# switches_annotated.net
KiCad netlist of a schematic drawn in EAGLE
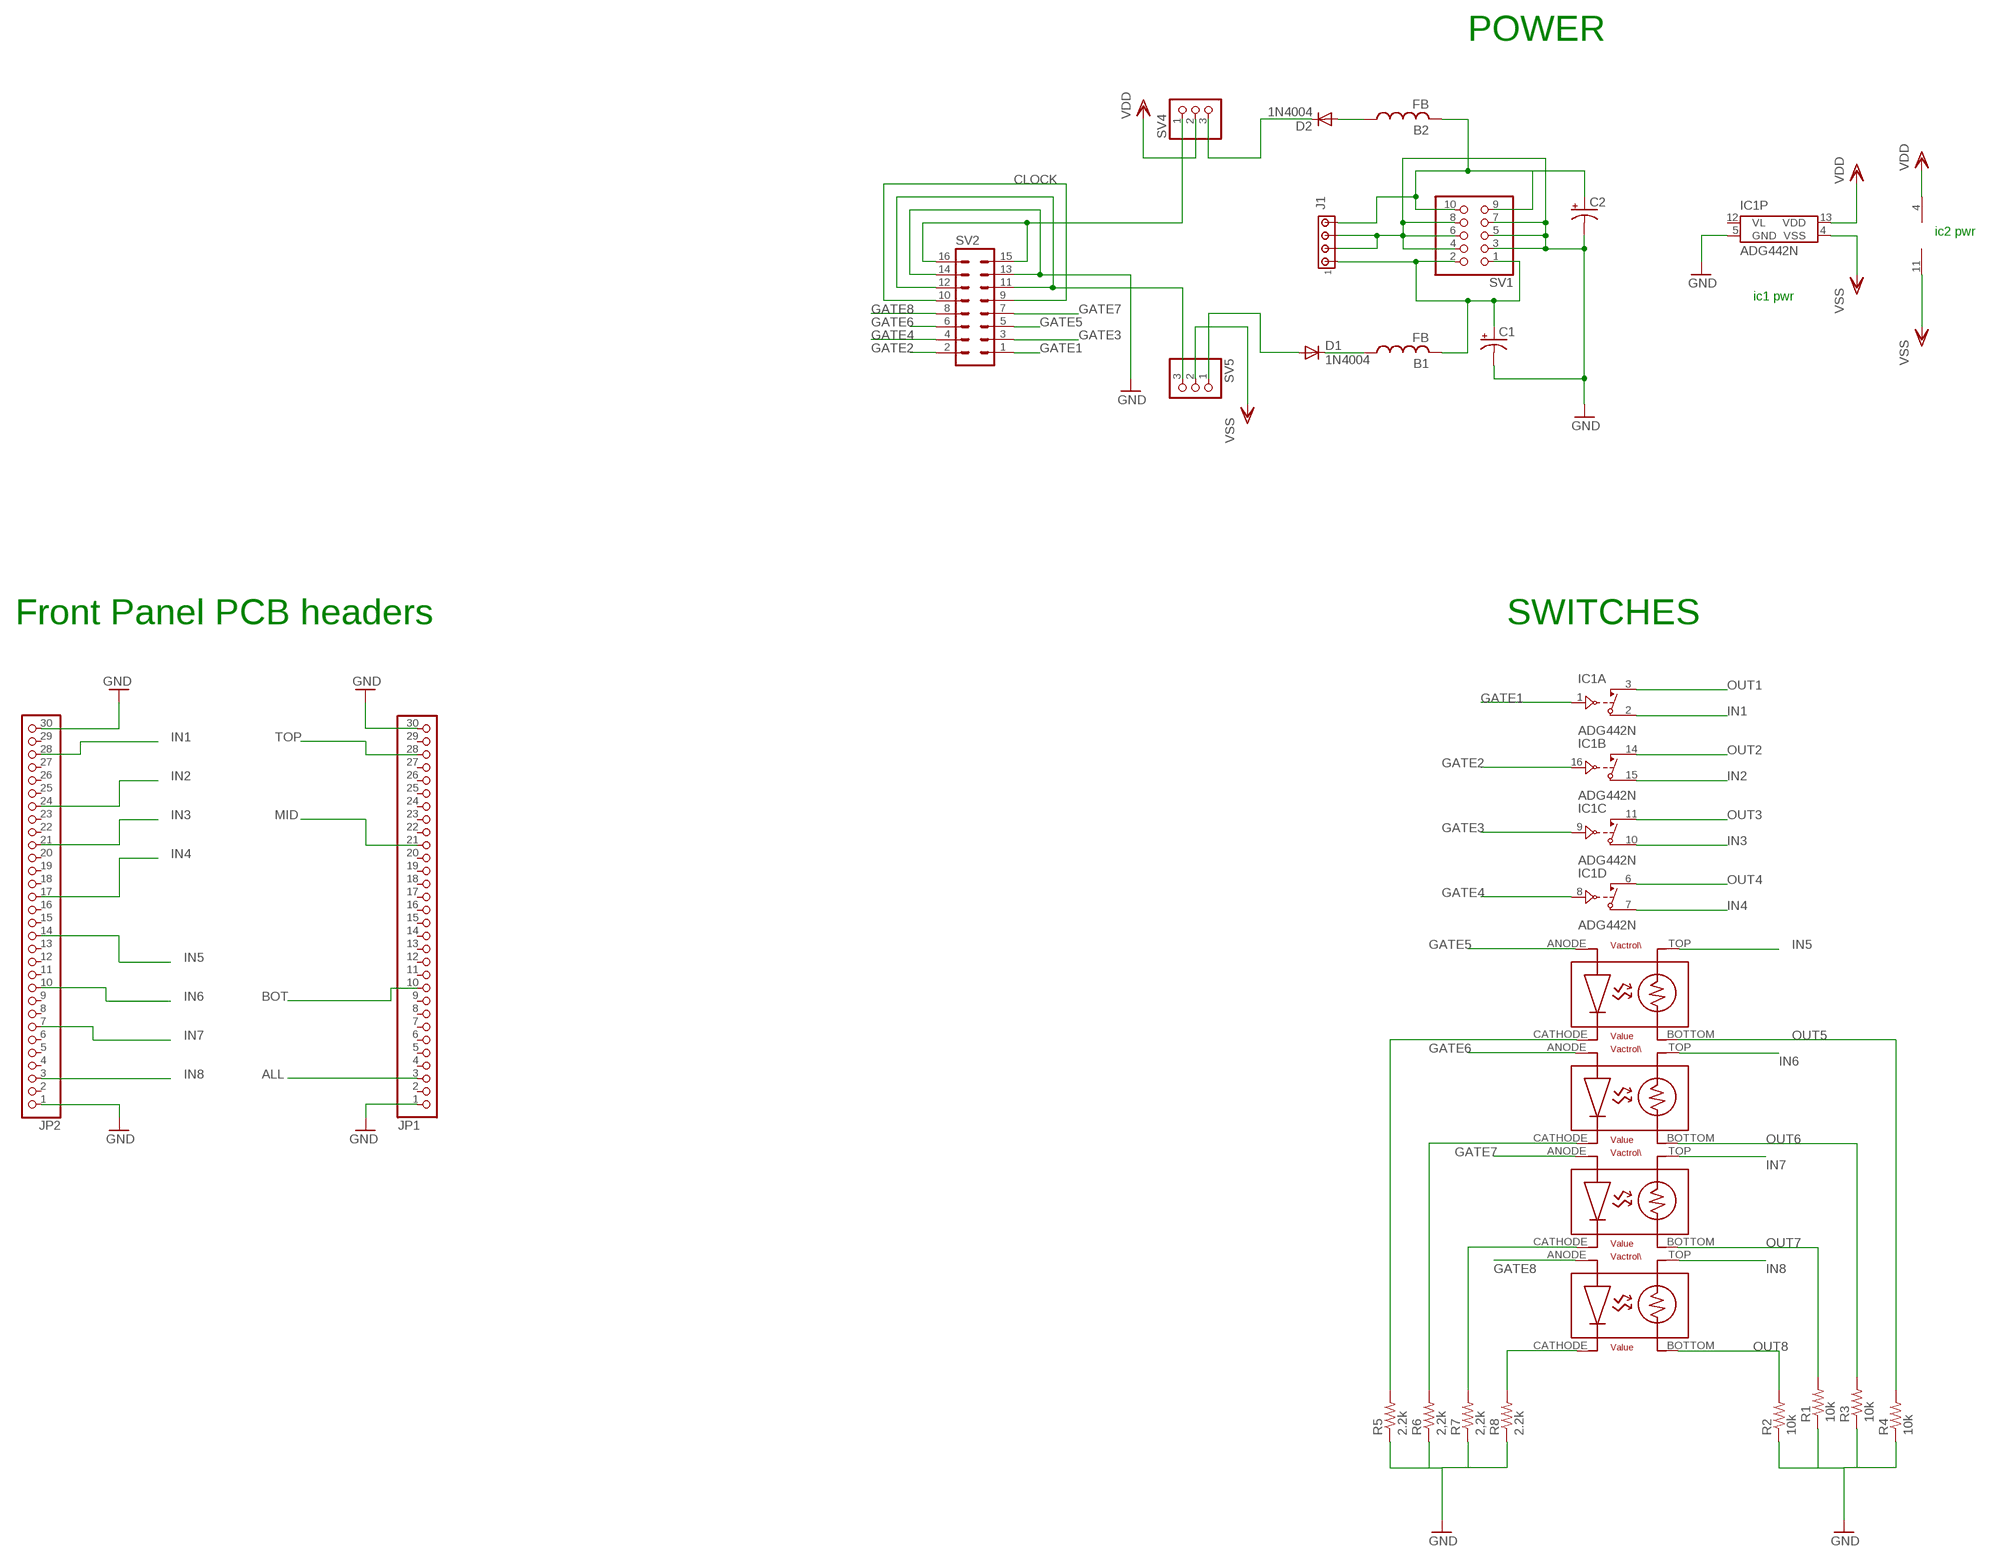
[diagram p0: schematic, sheet 1, part 1 of 2]
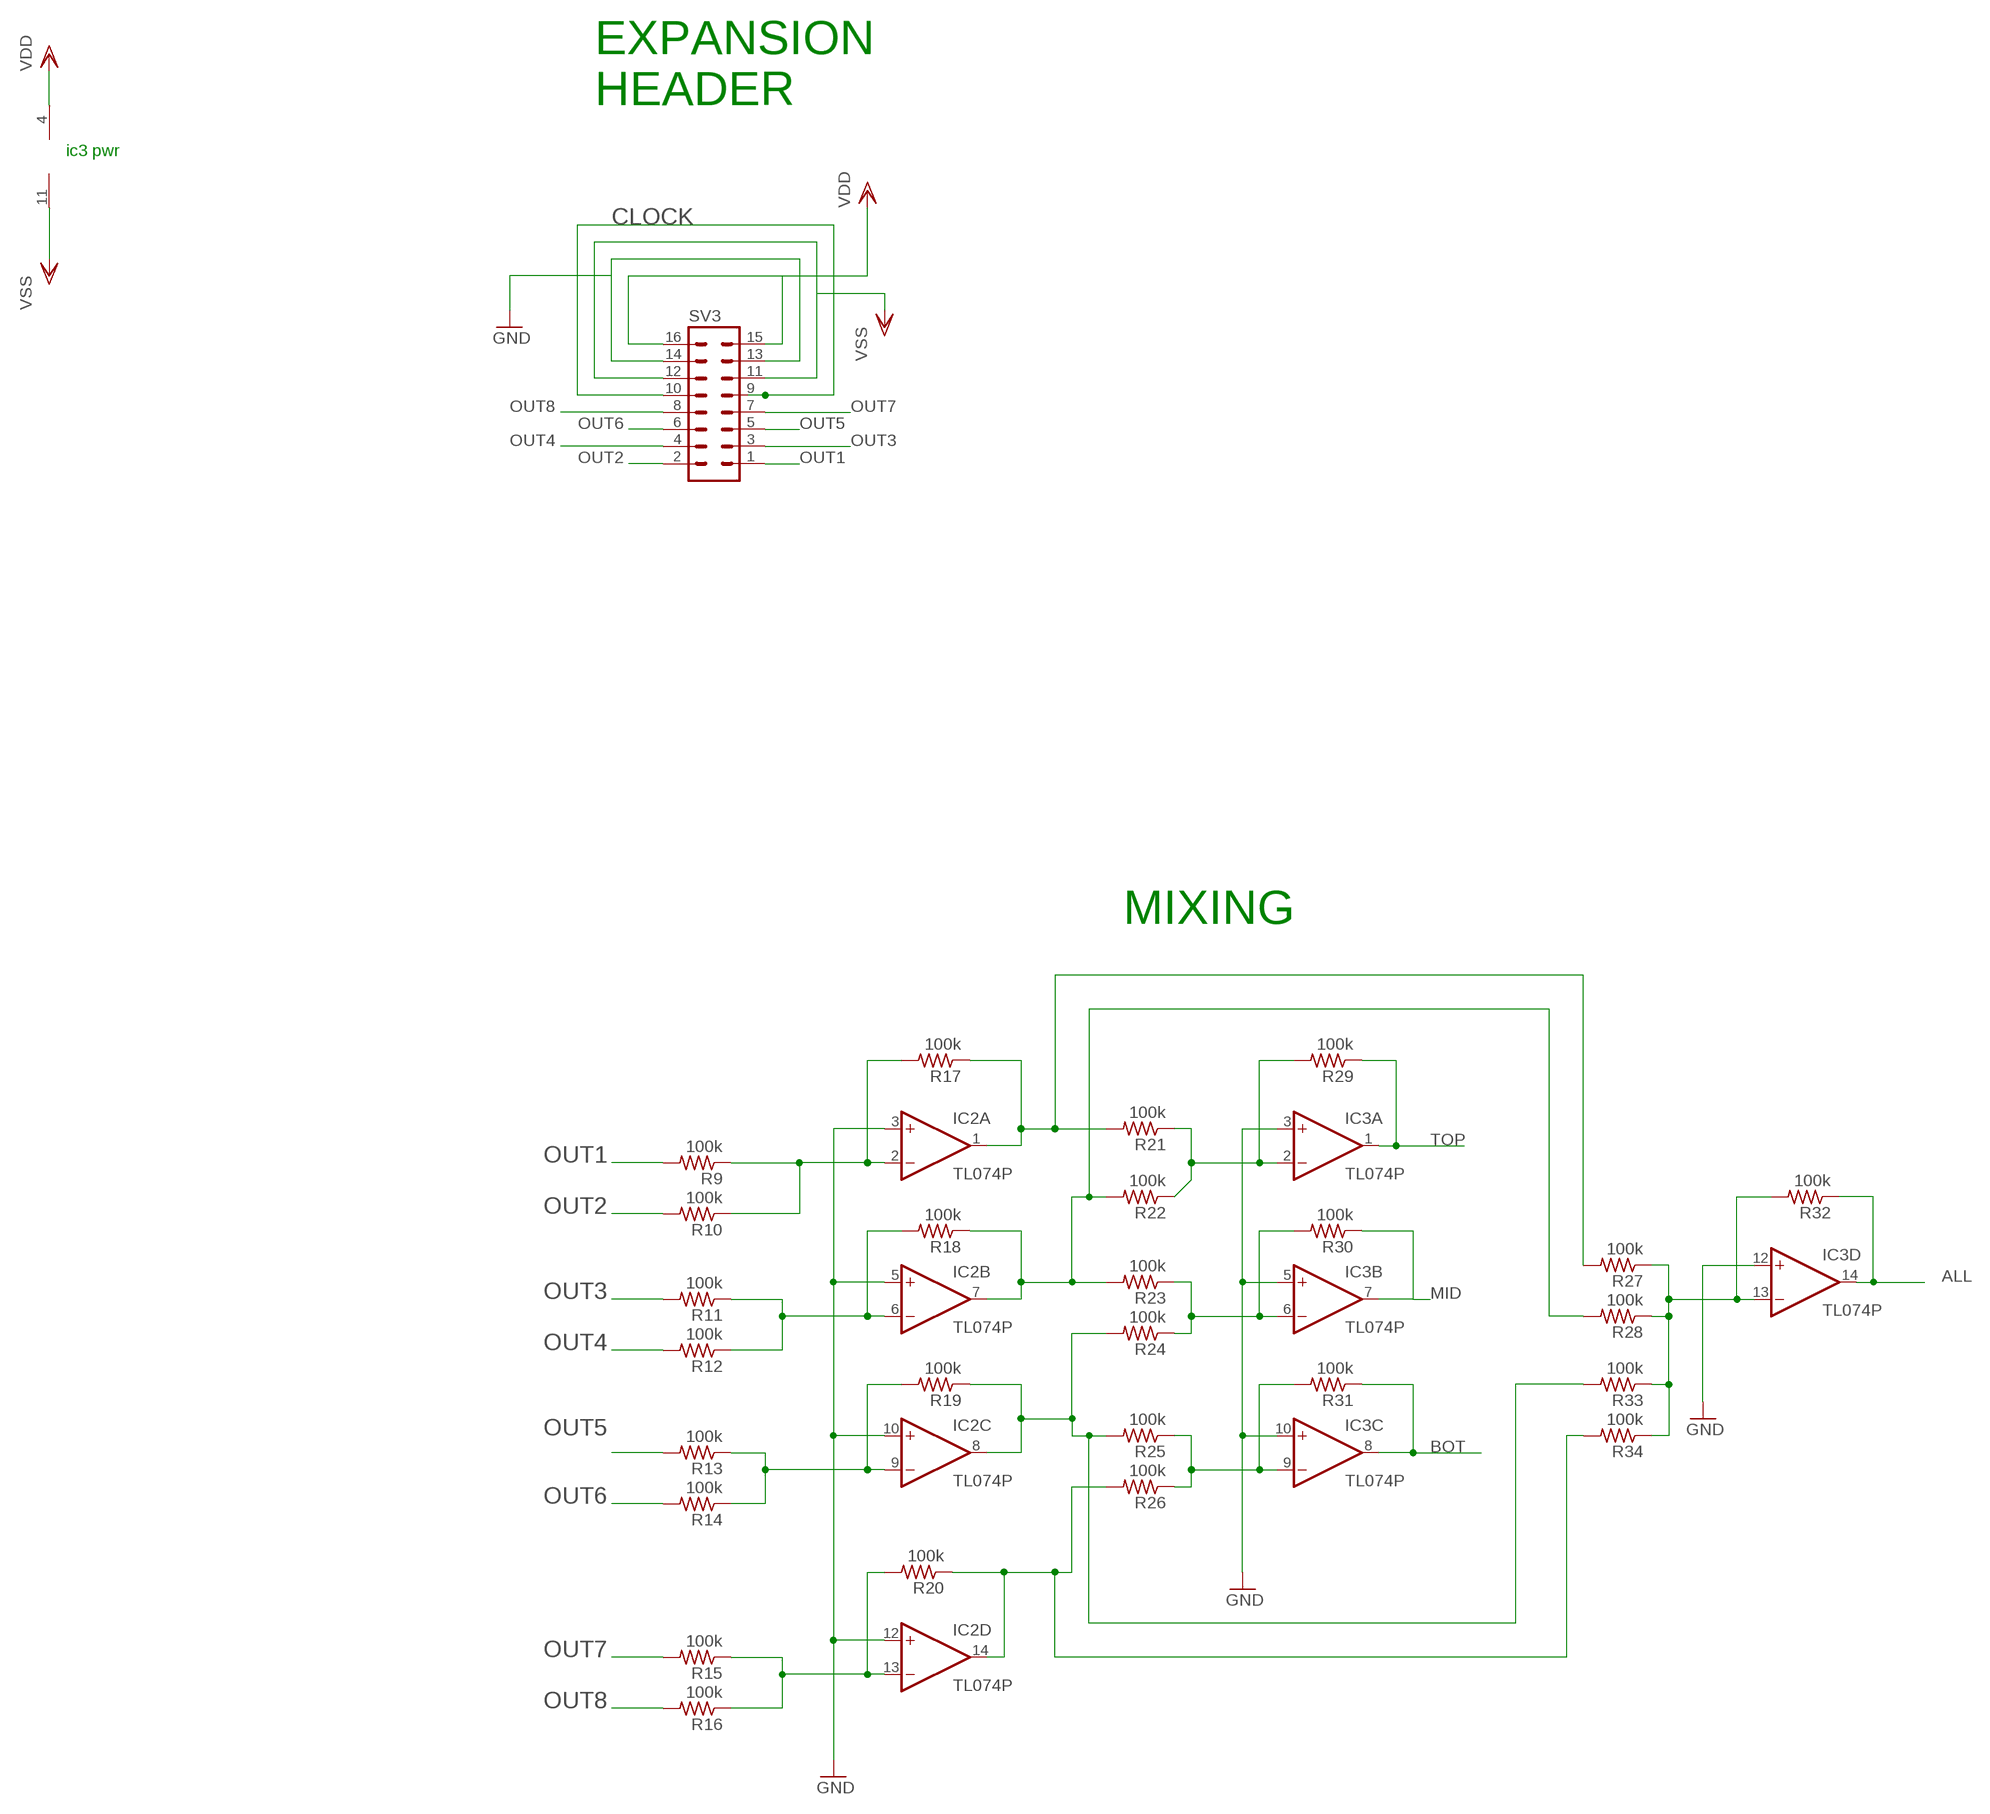
[diagram p1: schematic, sheet 1, part 2 of 2]

(export (version "E")
  (design (tool "Eeschema 10.0.6"))
  (components
    (comp (ref "B1") (value "FB") (footprint "eagle-import:FB") (libsource (lib "eagle-import") (part "FB")))
    (comp (ref "B2") (value "FB") (footprint "eagle-import:FB") (libsource (lib "eagle-import") (part "FB")))
    (comp (ref "C1")
      (value "CPOL-USE1.8-4")
      (footprint "eagle-import:E1,8-4")
      (libsource (lib "eagle-import") (part "CPOL-USE1.8-4"))
    )
    (comp (ref "C2")
      (value "CPOL-USE1.8-4")
      (footprint "eagle-import:E1,8-4")
      (libsource (lib "eagle-import") (part "CPOL-USE1.8-4"))
    )
    (comp (ref "D1")
      (value "1N4004")
      (footprint "eagle-import:DO41-10")
      (libsource (lib "eagle-import") (part "1N4004"))
    )
    (comp (ref "D2")
      (value "1N4004")
      (footprint "eagle-import:DO41-10")
      (libsource (lib "eagle-import") (part "1N4004"))
    )
    (comp (ref "IC1")
      (value "ADG442N")
      (footprint "eagle-import:DIL16")
      (fields (field (name "MF") "ALTERA CORPORATION") (field (name "MPN") "ADG411BN"))
      (libsource (lib "eagle-import") (part "ADG442N"))
    )
    (comp (ref "IC2")
      (value "TL074P")
      (footprint "eagle-import:DIL14")
      (libsource (lib "eagle-import") (part "TL074P"))
    )
    (comp (ref "IC3")
      (value "TL074P")
      (footprint "eagle-import:DIL14")
      (libsource (lib "eagle-import") (part "TL074P"))
    )
    (comp (ref "J1")
      (value "MTA04-156")
      (footprint "eagle-import:1X4MTA")
      (libsource (lib "eagle-import") (part "MTA04-156"))
    )
    (comp (ref "JP1")
      (value "PINHD-1X30")
      (footprint "eagle-import:1X30")
      (libsource (lib "eagle-import") (part "PINHD-1X30"))
    )
    (comp (ref "JP2")
      (value "PINHD-1X30")
      (footprint "eagle-import:1X30")
      (libsource (lib "eagle-import") (part "PINHD-1X30"))
    )
    (comp (ref "R1")
      (value "10k")
      (footprint "eagle-import:0204V")
      (libsource (lib "eagle-import") (part "R-US_0204/2V"))
    )
    (comp (ref "R2")
      (value "10k")
      (footprint "eagle-import:0204V")
      (libsource (lib "eagle-import") (part "R-US_0204/2V"))
    )
    (comp (ref "R3")
      (value "10k")
      (footprint "eagle-import:0204V")
      (libsource (lib "eagle-import") (part "R-US_0204/2V"))
    )
    (comp (ref "R4")
      (value "10k")
      (footprint "eagle-import:0204V")
      (libsource (lib "eagle-import") (part "R-US_0204/2V"))
    )
    (comp (ref "R5")
      (value "2.2k")
      (footprint "eagle-import:0204V")
      (libsource (lib "eagle-import") (part "R-US_0204/2V"))
    )
    (comp (ref "R6")
      (value "2,2k")
      (footprint "eagle-import:0204V")
      (libsource (lib "eagle-import") (part "R-US_0204/2V"))
    )
    (comp (ref "R7")
      (value "2,2k")
      (footprint "eagle-import:0204V")
      (libsource (lib "eagle-import") (part "R-US_0204/2V"))
    )
    (comp (ref "R8")
      (value "2.2k")
      (footprint "eagle-import:0204V")
      (libsource (lib "eagle-import") (part "R-US_0204/2V"))
    )
    (comp (ref "R9")
      (value "100k")
      (footprint "eagle-import:0204_7")
      (libsource (lib "eagle-import") (part "R-US_0204/7"))
    )
    (comp (ref "R10")
      (value "100k")
      (footprint "eagle-import:0204_7")
      (libsource (lib "eagle-import") (part "R-US_0204/7"))
    )
    (comp (ref "R11")
      (value "100k")
      (footprint "eagle-import:0204_7")
      (libsource (lib "eagle-import") (part "R-US_0204/7"))
    )
    (comp (ref "R12")
      (value "100k")
      (footprint "eagle-import:0204_7")
      (libsource (lib "eagle-import") (part "R-US_0204/7"))
    )
    (comp (ref "R13")
      (value "100k")
      (footprint "eagle-import:0204_7")
      (libsource (lib "eagle-import") (part "R-US_0204/7"))
    )
    (comp (ref "R14")
      (value "100k")
      (footprint "eagle-import:0204_7")
      (libsource (lib "eagle-import") (part "R-US_0204/7"))
    )
    (comp (ref "R15")
      (value "100k")
      (footprint "eagle-import:0204_7")
      (libsource (lib "eagle-import") (part "R-US_0204/7"))
    )
    (comp (ref "R16")
      (value "100k")
      (footprint "eagle-import:0204_7")
      (libsource (lib "eagle-import") (part "R-US_0204/7"))
    )
    (comp (ref "R17")
      (value "100k")
      (footprint "eagle-import:0204V")
      (libsource (lib "eagle-import") (part "R-US_0204/2V"))
    )
    (comp (ref "R18")
      (value "100k")
      (footprint "eagle-import:0204V")
      (libsource (lib "eagle-import") (part "R-US_0204/2V"))
    )
    (comp (ref "R19")
      (value "100k")
      (footprint "eagle-import:0204V")
      (libsource (lib "eagle-import") (part "R-US_0204/2V"))
    )
    (comp (ref "R20")
      (value "100k")
      (footprint "eagle-import:0204V")
      (libsource (lib "eagle-import") (part "R-US_0204/2V"))
    )
    (comp (ref "R21")
      (value "100k")
      (footprint "eagle-import:0204_7")
      (libsource (lib "eagle-import") (part "R-US_0204/7"))
    )
    (comp (ref "R22")
      (value "100k")
      (footprint "eagle-import:0204_7")
      (libsource (lib "eagle-import") (part "R-US_0204/7"))
    )
    (comp (ref "R23")
      (value "100k")
      (footprint "eagle-import:0204_7")
      (libsource (lib "eagle-import") (part "R-US_0204/7"))
    )
    (comp (ref "R24")
      (value "100k")
      (footprint "eagle-import:0204_7")
      (libsource (lib "eagle-import") (part "R-US_0204/7"))
    )
    (comp (ref "R25")
      (value "100k")
      (footprint "eagle-import:0204V")
      (libsource (lib "eagle-import") (part "R-US_0204/2V"))
    )
    (comp (ref "R26")
      (value "100k")
      (footprint "eagle-import:0204_7")
      (libsource (lib "eagle-import") (part "R-US_0204/7"))
    )
    (comp (ref "R27")
      (value "100k")
      (footprint "eagle-import:0204_7")
      (libsource (lib "eagle-import") (part "R-US_0204/7"))
    )
    (comp (ref "R28")
      (value "100k")
      (footprint "eagle-import:0204_7")
      (libsource (lib "eagle-import") (part "R-US_0204/7"))
    )
    (comp (ref "R29")
      (value "100k")
      (footprint "eagle-import:0204V")
      (libsource (lib "eagle-import") (part "R-US_0204/2V"))
    )
    (comp (ref "R30")
      (value "100k")
      (footprint "eagle-import:0204V")
      (libsource (lib "eagle-import") (part "R-US_0204/2V"))
    )
    (comp (ref "R31")
      (value "100k")
      (footprint "eagle-import:0204V")
      (libsource (lib "eagle-import") (part "R-US_0204/2V"))
    )
    (comp (ref "R32")
      (value "100k")
      (footprint "eagle-import:0204V")
      (libsource (lib "eagle-import") (part "R-US_0204/2V"))
    )
    (comp (ref "R33")
      (value "100k")
      (footprint "eagle-import:0204V")
      (libsource (lib "eagle-import") (part "R-US_0204/2V"))
    )
    (comp (ref "R34")
      (value "100k")
      (footprint "eagle-import:0204V")
      (libsource (lib "eagle-import") (part "R-US_0204/2V"))
    )
    (comp (ref "SV1")
      (value "PINHD-2X5")
      (footprint "eagle-import:2X05")
      (libsource (lib "eagle-import") (part "PINHD-2X5"))
    )
    (comp (ref "SV2")
      (value "MA08-2")
      (footprint "eagle-import:MA08-2")
      (libsource (lib "eagle-import") (part "MA08-2"))
    )
    (comp (ref "SV3")
      (value "MA08-2")
      (footprint "eagle-import:MA08-2")
      (libsource (lib "eagle-import") (part "MA08-2"))
    )
    (comp (ref "SV4")
      (value "PINHD-1X3")
      (footprint "eagle-import:1X03")
      (libsource (lib "eagle-import") (part "PINHD-1X3"))
    )
    (comp (ref "SV5")
      (value "PINHD-1X3")
      (footprint "eagle-import:1X03")
      (libsource (lib "eagle-import") (part "PINHD-1X3"))
    )
    (comp (ref "U$1")
      (value "VACTROL")
      (footprint "eagle-import:VACTROL")
      (libsource (lib "eagle-import") (part "VACTROL"))
    )
    (comp (ref "U$2")
      (value "VACTROL")
      (footprint "eagle-import:VACTROL")
      (libsource (lib "eagle-import") (part "VACTROL"))
    )
    (comp (ref "U$3")
      (value "VACTROL")
      (footprint "eagle-import:VACTROL")
      (libsource (lib "eagle-import") (part "VACTROL"))
    )
    (comp (ref "U$4")
      (value "VACTROL")
      (footprint "eagle-import:VACTROL")
      (libsource (lib "eagle-import") (part "VACTROL"))
    )
  )
  (nets
    (net (code "1") (name "/ALL") (class "Default")
      (node (ref "IC3") (pin "14") (pinfunction "OUT_14") (pintype "output"))
      (node (ref "JP1") (pin "3") (pinfunction "3_3") (pintype "passive"))
      (node (ref "R32") (pin "1") (pinfunction "1_1") (pintype "passive"))
    )
    (net (code "2") (name "/BOT") (class "Default")
      (node (ref "IC3") (pin "8") (pinfunction "OUT_8") (pintype "output"))
      (node (ref "JP1") (pin "10") (pinfunction "10_10") (pintype "passive"))
      (node (ref "R31") (pin "1") (pinfunction "1_1") (pintype "passive"))
    )
    (net (code "3") (name "/CLOCK") (class "Default")
      (node (ref "SV2") (pin "10") (pinfunction "10_10") (pintype "passive"))
      (node (ref "SV2") (pin "9") (pinfunction "9_9") (pintype "passive"))
      (node (ref "SV3") (pin "10") (pinfunction "10_10") (pintype "passive"))
      (node (ref "SV3") (pin "9") (pinfunction "9_9") (pintype "passive"))
    )
    (net (code "4") (name "/GATE1") (class "Default")
      (node (ref "IC1") (pin "1") (pinfunction "IN_1") (pintype "input"))
      (node (ref "SV2") (pin "1") (pinfunction "1_1") (pintype "passive"))
    )
    (net (code "5") (name "/GATE2") (class "Default")
      (node (ref "IC1") (pin "16") (pinfunction "IN_16") (pintype "input"))
      (node (ref "SV2") (pin "2") (pinfunction "2_2") (pintype "passive"))
    )
    (net (code "6") (name "/GATE3") (class "Default")
      (node (ref "IC1") (pin "9") (pinfunction "IN_9") (pintype "input"))
      (node (ref "SV2") (pin "3") (pinfunction "3_3") (pintype "passive"))
    )
    (net (code "7") (name "/GATE4") (class "Default")
      (node (ref "IC1") (pin "8") (pinfunction "IN_8") (pintype "input"))
      (node (ref "SV2") (pin "4") (pinfunction "4_4") (pintype "passive"))
    )
    (net (code "8") (name "/GATE5") (class "Default")
      (node (ref "SV2") (pin "5") (pinfunction "5_5") (pintype "passive"))
      (node (ref "U$1") (pin "ANODE") (pinfunction "ANODE_ANODE") (pintype "bidirectional"))
    )
    (net (code "9") (name "/GATE6") (class "Default")
      (node (ref "SV2") (pin "6") (pinfunction "6_6") (pintype "passive"))
      (node (ref "U$2") (pin "ANODE") (pinfunction "ANODE_ANODE") (pintype "bidirectional"))
    )
    (net (code "10") (name "/GATE7") (class "Default")
      (node (ref "SV2") (pin "7") (pinfunction "7_7") (pintype "passive"))
      (node (ref "U$3") (pin "ANODE") (pinfunction "ANODE_ANODE") (pintype "bidirectional"))
    )
    (net (code "11") (name "/GATE8") (class "Default")
      (node (ref "SV2") (pin "8") (pinfunction "8_8") (pintype "passive"))
      (node (ref "U$4") (pin "ANODE") (pinfunction "ANODE_ANODE") (pintype "bidirectional"))
    )
    (net (code "12") (name "/IN1") (class "Default")
      (node (ref "IC1") (pin "2") (pinfunction "D_2") (pintype "passive"))
      (node (ref "JP2") (pin "28") (pinfunction "28_28") (pintype "passive"))
    )
    (net (code "13") (name "/IN2") (class "Default")
      (node (ref "IC1") (pin "15") (pinfunction "D_15") (pintype "passive"))
      (node (ref "JP2") (pin "24") (pinfunction "24_24") (pintype "passive"))
    )
    (net (code "14") (name "/IN3") (class "Default")
      (node (ref "IC1") (pin "10") (pinfunction "D_10") (pintype "passive"))
      (node (ref "JP2") (pin "21") (pinfunction "21_21") (pintype "passive"))
    )
    (net (code "15") (name "/IN4") (class "Default")
      (node (ref "IC1") (pin "7") (pinfunction "D_7") (pintype "passive"))
      (node (ref "JP2") (pin "17") (pinfunction "17_17") (pintype "passive"))
    )
    (net (code "16") (name "/IN5") (class "Default")
      (node (ref "JP2") (pin "14") (pinfunction "14_14") (pintype "passive"))
      (node (ref "U$1") (pin "TOP") (pinfunction "TOP_TOP") (pintype "bidirectional"))
    )
    (net (code "17") (name "/IN6") (class "Default")
      (node (ref "JP2") (pin "10") (pinfunction "10_10") (pintype "passive"))
      (node (ref "U$2") (pin "TOP") (pinfunction "TOP_TOP") (pintype "bidirectional"))
    )
    (net (code "18") (name "/IN7") (class "Default")
      (node (ref "JP2") (pin "7") (pinfunction "7_7") (pintype "passive"))
      (node (ref "U$3") (pin "TOP") (pinfunction "TOP_TOP") (pintype "bidirectional"))
    )
    (net (code "19") (name "/IN8") (class "Default")
      (node (ref "JP2") (pin "3") (pinfunction "3_3") (pintype "passive"))
      (node (ref "U$4") (pin "TOP") (pinfunction "TOP_TOP") (pintype "bidirectional"))
    )
    (net (code "20") (name "/MID") (class "Default")
      (node (ref "IC3") (pin "7") (pinfunction "OUT_7") (pintype "output"))
      (node (ref "JP1") (pin "21") (pinfunction "21_21") (pintype "passive"))
      (node (ref "R30") (pin "1") (pinfunction "1_1") (pintype "passive"))
    )
    (net (code "21") (name "/OUT1") (class "Default")
      (node (ref "IC1") (pin "3") (pinfunction "S_3") (pintype "passive"))
      (node (ref "R9") (pin "2") (pinfunction "2_2") (pintype "passive"))
      (node (ref "SV3") (pin "1") (pinfunction "1_1") (pintype "passive"))
    )
    (net (code "22") (name "/OUT2") (class "Default")
      (node (ref "IC1") (pin "14") (pinfunction "S_14") (pintype "passive"))
      (node (ref "R10") (pin "2") (pinfunction "2_2") (pintype "passive"))
      (node (ref "SV3") (pin "2") (pinfunction "2_2") (pintype "passive"))
    )
    (net (code "23") (name "/OUT3") (class "Default")
      (node (ref "IC1") (pin "11") (pinfunction "S_11") (pintype "passive"))
      (node (ref "R11") (pin "2") (pinfunction "2_2") (pintype "passive"))
      (node (ref "SV3") (pin "3") (pinfunction "3_3") (pintype "passive"))
    )
    (net (code "24") (name "/OUT4") (class "Default")
      (node (ref "IC1") (pin "6") (pinfunction "S_6") (pintype "passive"))
      (node (ref "R12") (pin "2") (pinfunction "2_2") (pintype "passive"))
      (node (ref "SV3") (pin "4") (pinfunction "4_4") (pintype "passive"))
    )
    (net (code "25") (name "/OUT5") (class "Default")
      (node (ref "R13") (pin "2") (pinfunction "2_2") (pintype "passive"))
      (node (ref "R4") (pin "2") (pinfunction "2_2") (pintype "passive"))
      (node (ref "SV3") (pin "5") (pinfunction "5_5") (pintype "passive"))
      (node (ref "U$1") (pin "BOTTOM") (pinfunction "BOTTOM_BOTTOM") (pintype "bidirectional"))
    )
    (net (code "26") (name "/OUT6") (class "Default")
      (node (ref "R14") (pin "2") (pinfunction "2_2") (pintype "passive"))
      (node (ref "R3") (pin "2") (pinfunction "2_2") (pintype "passive"))
      (node (ref "SV3") (pin "6") (pinfunction "6_6") (pintype "passive"))
      (node (ref "U$2") (pin "BOTTOM") (pinfunction "BOTTOM_BOTTOM") (pintype "bidirectional"))
    )
    (net (code "27") (name "/OUT7") (class "Default")
      (node (ref "R1") (pin "2") (pinfunction "2_2") (pintype "passive"))
      (node (ref "R15") (pin "2") (pinfunction "2_2") (pintype "passive"))
      (node (ref "SV3") (pin "7") (pinfunction "7_7") (pintype "passive"))
      (node (ref "U$3") (pin "BOTTOM") (pinfunction "BOTTOM_BOTTOM") (pintype "bidirectional"))
    )
    (net (code "28") (name "/OUT8") (class "Default")
      (node (ref "R16") (pin "2") (pinfunction "2_2") (pintype "passive"))
      (node (ref "R2") (pin "2") (pinfunction "2_2") (pintype "passive"))
      (node (ref "SV3") (pin "8") (pinfunction "8_8") (pintype "passive"))
      (node (ref "U$4") (pin "BOTTOM") (pinfunction "BOTTOM_BOTTOM") (pintype "bidirectional"))
    )
    (net (code "29") (name "/TOP") (class "Default")
      (node (ref "IC3") (pin "1") (pinfunction "OUT_1") (pintype "output"))
      (node (ref "JP1") (pin "28") (pinfunction "28_28") (pintype "passive"))
      (node (ref "R29") (pin "1") (pinfunction "1_1") (pintype "passive"))
    )
    (net (code "30") (name "/VL") (class "Default")
      (node (ref "IC1") (pin "12") (pinfunction "VL_12") (pintype "power_in"))
    )
    (net (code "31") (name "GND") (class "Default")
      (node (ref "C1") (pin "-") (pinfunction "-_-") (pintype "passive"))
      (node (ref "C2") (pin "-") (pinfunction "-_-") (pintype "passive"))
      (node (ref "IC1") (pin "5") (pinfunction "GND_5") (pintype "power_in"))
      (node (ref "IC2") (pin "10") (pinfunction "+IN_10") (pintype "input"))
      (node (ref "IC2") (pin "12") (pinfunction "+IN_12") (pintype "input"))
      (node (ref "IC2") (pin "3") (pinfunction "+IN_3") (pintype "input"))
      (node (ref "IC2") (pin "5") (pinfunction "+IN_5") (pintype "input"))
      (node (ref "IC3") (pin "10") (pinfunction "+IN_10") (pintype "input"))
      (node (ref "IC3") (pin "12") (pinfunction "+IN_12") (pintype "input"))
      (node (ref "IC3") (pin "3") (pinfunction "+IN_3") (pintype "input"))
      (node (ref "IC3") (pin "5") (pinfunction "+IN_5") (pintype "input"))
      (node (ref "J1") (pin "2") (pinfunction "2_2") (pintype "passive"))
      (node (ref "J1") (pin "3") (pinfunction "3_3") (pintype "passive"))
      (node (ref "JP1") (pin "1") (pinfunction "1_1") (pintype "passive"))
      (node (ref "JP1") (pin "30") (pinfunction "30_30") (pintype "passive"))
      (node (ref "JP2") (pin "1") (pinfunction "1_1") (pintype "passive"))
      (node (ref "JP2") (pin "30") (pinfunction "30_30") (pintype "passive"))
      (node (ref "R1") (pin "1") (pinfunction "1_1") (pintype "passive"))
      (node (ref "R2") (pin "1") (pinfunction "1_1") (pintype "passive"))
      (node (ref "R3") (pin "1") (pinfunction "1_1") (pintype "passive"))
      (node (ref "R4") (pin "1") (pinfunction "1_1") (pintype "passive"))
      (node (ref "R5") (pin "1") (pinfunction "1_1") (pintype "passive"))
      (node (ref "R6") (pin "1") (pinfunction "1_1") (pintype "passive"))
      (node (ref "R7") (pin "1") (pinfunction "1_1") (pintype "passive"))
      (node (ref "R8") (pin "1") (pinfunction "1_1") (pintype "passive"))
      (node (ref "SV1") (pin "3") (pinfunction "3_3") (pintype "passive"))
      (node (ref "SV1") (pin "4") (pinfunction "4_4") (pintype "passive"))
      (node (ref "SV1") (pin "5") (pinfunction "5_5") (pintype "passive"))
      (node (ref "SV1") (pin "6") (pinfunction "6_6") (pintype "passive"))
      (node (ref "SV1") (pin "7") (pinfunction "7_7") (pintype "passive"))
      (node (ref "SV1") (pin "8") (pinfunction "8_8") (pintype "passive"))
      (node (ref "SV2") (pin "13") (pinfunction "13_13") (pintype "passive"))
      (node (ref "SV2") (pin "14") (pinfunction "14_14") (pintype "passive"))
      (node (ref "SV3") (pin "13") (pinfunction "13_13") (pintype "passive"))
      (node (ref "SV3") (pin "14") (pinfunction "14_14") (pintype "passive"))
    )
    (net (code "32") (name "Net-(B1-1)") (class "Default")
      (node (ref "B1") (pin "P$1") (pinfunction "1_P$1") (pintype "passive"))
      (node (ref "D1") (pin "C") (pinfunction "C_C") (pintype "passive"))
    )
    (net (code "33") (name "Net-(B1-2)") (class "Default")
      (node (ref "B1") (pin "P$2") (pinfunction "2_P$2") (pintype "passive"))
      (node (ref "C1") (pin "+") (pinfunction "+_+") (pintype "passive"))
      (node (ref "J1") (pin "1") (pinfunction "1_1") (pintype "passive"))
      (node (ref "SV1") (pin "1") (pinfunction "1_1") (pintype "passive"))
      (node (ref "SV1") (pin "2") (pinfunction "2_2") (pintype "passive"))
    )
    (net (code "34") (name "Net-(B2-1)") (class "Default")
      (node (ref "B2") (pin "P$1") (pinfunction "1_P$1") (pintype "passive"))
      (node (ref "D2") (pin "A") (pinfunction "A_A") (pintype "passive"))
    )
    (net (code "35") (name "Net-(B2-2)") (class "Default")
      (node (ref "B2") (pin "P$2") (pinfunction "2_P$2") (pintype "passive"))
      (node (ref "C2") (pin "+") (pinfunction "+_+") (pintype "passive"))
      (node (ref "J1") (pin "4") (pinfunction "4_4") (pintype "passive"))
      (node (ref "SV1") (pin "10") (pinfunction "10_10") (pintype "passive"))
      (node (ref "SV1") (pin "9") (pinfunction "9_9") (pintype "passive"))
    )
    (net (code "36") (name "Net-(D1-PadA)") (class "Default")
      (node (ref "D1") (pin "A") (pinfunction "A_A") (pintype "passive"))
      (node (ref "SV5") (pin "1") (pinfunction "1_1") (pintype "passive"))
    )
    (net (code "37") (name "Net-(D2-PadC)") (class "Default")
      (node (ref "D2") (pin "C") (pinfunction "C_C") (pintype "passive"))
      (node (ref "SV4") (pin "3") (pinfunction "3_3") (pintype "passive"))
    )
    (net (code "38") (name "Net-(IC2A--IN)") (class "Default")
      (node (ref "IC2") (pin "2") (pinfunction "-IN_2") (pintype "input"))
      (node (ref "R10") (pin "1") (pinfunction "1_1") (pintype "passive"))
      (node (ref "R17") (pin "2") (pinfunction "2_2") (pintype "passive"))
      (node (ref "R9") (pin "1") (pinfunction "1_1") (pintype "passive"))
    )
    (net (code "39") (name "Net-(IC2A-OUT)") (class "Default")
      (node (ref "IC2") (pin "1") (pinfunction "OUT_1") (pintype "output"))
      (node (ref "R17") (pin "1") (pinfunction "1_1") (pintype "passive"))
      (node (ref "R21") (pin "2") (pinfunction "2_2") (pintype "passive"))
      (node (ref "R27") (pin "2") (pinfunction "2_2") (pintype "passive"))
    )
    (net (code "40") (name "Net-(IC2B--IN)") (class "Default")
      (node (ref "IC2") (pin "6") (pinfunction "-IN_6") (pintype "input"))
      (node (ref "R11") (pin "1") (pinfunction "1_1") (pintype "passive"))
      (node (ref "R12") (pin "1") (pinfunction "1_1") (pintype "passive"))
      (node (ref "R18") (pin "2") (pinfunction "2_2") (pintype "passive"))
    )
    (net (code "41") (name "Net-(IC2B-OUT)") (class "Default")
      (node (ref "IC2") (pin "7") (pinfunction "OUT_7") (pintype "output"))
      (node (ref "R18") (pin "1") (pinfunction "1_1") (pintype "passive"))
      (node (ref "R22") (pin "2") (pinfunction "2_2") (pintype "passive"))
      (node (ref "R23") (pin "2") (pinfunction "2_2") (pintype "passive"))
      (node (ref "R28") (pin "2") (pinfunction "2_2") (pintype "passive"))
    )
    (net (code "42") (name "Net-(IC2C--IN)") (class "Default")
      (node (ref "IC2") (pin "9") (pinfunction "-IN_9") (pintype "input"))
      (node (ref "R13") (pin "1") (pinfunction "1_1") (pintype "passive"))
      (node (ref "R14") (pin "1") (pinfunction "1_1") (pintype "passive"))
      (node (ref "R19") (pin "2") (pinfunction "2_2") (pintype "passive"))
    )
    (net (code "43") (name "Net-(IC2C-OUT)") (class "Default")
      (node (ref "IC2") (pin "8") (pinfunction "OUT_8") (pintype "output"))
      (node (ref "R19") (pin "1") (pinfunction "1_1") (pintype "passive"))
      (node (ref "R24") (pin "2") (pinfunction "2_2") (pintype "passive"))
      (node (ref "R25") (pin "2") (pinfunction "2_2") (pintype "passive"))
      (node (ref "R33") (pin "2") (pinfunction "2_2") (pintype "passive"))
    )
    (net (code "44") (name "Net-(IC2D--IN)") (class "Default")
      (node (ref "IC2") (pin "13") (pinfunction "-IN_13") (pintype "input"))
      (node (ref "R15") (pin "1") (pinfunction "1_1") (pintype "passive"))
      (node (ref "R16") (pin "1") (pinfunction "1_1") (pintype "passive"))
      (node (ref "R20") (pin "2") (pinfunction "2_2") (pintype "passive"))
    )
    (net (code "45") (name "Net-(IC2D-OUT)") (class "Default")
      (node (ref "IC2") (pin "14") (pinfunction "OUT_14") (pintype "output"))
      (node (ref "R20") (pin "1") (pinfunction "1_1") (pintype "passive"))
      (node (ref "R26") (pin "2") (pinfunction "2_2") (pintype "passive"))
      (node (ref "R34") (pin "2") (pinfunction "2_2") (pintype "passive"))
    )
    (net (code "46") (name "Net-(IC3A--IN)") (class "Default")
      (node (ref "IC3") (pin "2") (pinfunction "-IN_2") (pintype "input"))
      (node (ref "R21") (pin "1") (pinfunction "1_1") (pintype "passive"))
      (node (ref "R22") (pin "1") (pinfunction "1_1") (pintype "passive"))
      (node (ref "R29") (pin "2") (pinfunction "2_2") (pintype "passive"))
    )
    (net (code "47") (name "Net-(IC3B--IN)") (class "Default")
      (node (ref "IC3") (pin "6") (pinfunction "-IN_6") (pintype "input"))
      (node (ref "R23") (pin "1") (pinfunction "1_1") (pintype "passive"))
      (node (ref "R24") (pin "1") (pinfunction "1_1") (pintype "passive"))
      (node (ref "R30") (pin "2") (pinfunction "2_2") (pintype "passive"))
    )
    (net (code "48") (name "Net-(IC3C--IN)") (class "Default")
      (node (ref "IC3") (pin "9") (pinfunction "-IN_9") (pintype "input"))
      (node (ref "R25") (pin "1") (pinfunction "1_1") (pintype "passive"))
      (node (ref "R26") (pin "1") (pinfunction "1_1") (pintype "passive"))
      (node (ref "R31") (pin "2") (pinfunction "2_2") (pintype "passive"))
    )
    (net (code "49") (name "Net-(IC3D--IN)") (class "Default")
      (node (ref "IC3") (pin "13") (pinfunction "-IN_13") (pintype "input"))
      (node (ref "R27") (pin "1") (pinfunction "1_1") (pintype "passive"))
      (node (ref "R28") (pin "1") (pinfunction "1_1") (pintype "passive"))
      (node (ref "R32") (pin "2") (pinfunction "2_2") (pintype "passive"))
      (node (ref "R33") (pin "1") (pinfunction "1_1") (pintype "passive"))
      (node (ref "R34") (pin "1") (pinfunction "1_1") (pintype "passive"))
    )
    (net (code "50") (name "Net-(R5-Pad2)") (class "Default")
      (node (ref "R5") (pin "2") (pinfunction "2_2") (pintype "passive"))
      (node (ref "U$1") (pin "CATHODE") (pinfunction "CATHODE_CATHODE") (pintype "bidirectional"))
    )
    (net (code "51") (name "Net-(R6-Pad2)") (class "Default")
      (node (ref "R6") (pin "2") (pinfunction "2_2") (pintype "passive"))
      (node (ref "U$2") (pin "CATHODE") (pinfunction "CATHODE_CATHODE") (pintype "bidirectional"))
    )
    (net (code "52") (name "Net-(R7-Pad2)") (class "Default")
      (node (ref "R7") (pin "2") (pinfunction "2_2") (pintype "passive"))
      (node (ref "U$3") (pin "CATHODE") (pinfunction "CATHODE_CATHODE") (pintype "bidirectional"))
    )
    (net (code "53") (name "Net-(R8-Pad2)") (class "Default")
      (node (ref "R8") (pin "2") (pinfunction "2_2") (pintype "passive"))
      (node (ref "U$4") (pin "CATHODE") (pinfunction "CATHODE_CATHODE") (pintype "bidirectional"))
    )
    (net (code "54") (name "Net-(SV2-Pad11)") (class "Default")
      (node (ref "SV2") (pin "11") (pinfunction "11_11") (pintype "passive"))
      (node (ref "SV2") (pin "12") (pinfunction "12_12") (pintype "passive"))
      (node (ref "SV5") (pin "3") (pinfunction "3_3") (pintype "passive"))
    )
    (net (code "55") (name "Net-(SV2-Pad15)") (class "Default")
      (node (ref "SV2") (pin "15") (pinfunction "15_15") (pintype "passive"))
      (node (ref "SV2") (pin "16") (pinfunction "16_16") (pintype "passive"))
      (node (ref "SV4") (pin "1") (pinfunction "1_1") (pintype "passive"))
    )
    (net (code "56") (name "VDD") (class "Default")
      (node (ref "IC1") (pin "13") (pinfunction "VDD_13") (pintype "power_in"))
      (node (ref "IC2") (pin "4") (pinfunction "V+_4") (pintype "power_in"))
      (node (ref "IC3") (pin "4") (pinfunction "V+_4") (pintype "power_in"))
      (node (ref "SV3") (pin "15") (pinfunction "15_15") (pintype "passive"))
      (node (ref "SV3") (pin "16") (pinfunction "16_16") (pintype "passive"))
      (node (ref "SV4") (pin "2") (pinfunction "2_2") (pintype "passive"))
    )
    (net (code "57") (name "VSS") (class "Default")
      (node (ref "IC1") (pin "4") (pinfunction "VSS_4") (pintype "power_in"))
      (node (ref "IC2") (pin "11") (pinfunction "V-_11") (pintype "power_in"))
      (node (ref "IC3") (pin "11") (pinfunction "V-_11") (pintype "power_in"))
      (node (ref "SV3") (pin "11") (pinfunction "11_11") (pintype "passive"))
      (node (ref "SV3") (pin "12") (pinfunction "12_12") (pintype "passive"))
      (node (ref "SV5") (pin "2") (pinfunction "2_2") (pintype "passive"))
    )
    (net (code "58") (name "unconnected-(JP1-Pad2)") (class "Default")
      (node (ref "JP1") (pin "2") (pinfunction "2_2") (pintype "passive"))
    )
    (net (code "59") (name "unconnected-(JP1-Pad4)") (class "Default")
      (node (ref "JP1") (pin "4") (pinfunction "4_4") (pintype "passive"))
    )
    (net (code "60") (name "unconnected-(JP1-Pad5)") (class "Default")
      (node (ref "JP1") (pin "5") (pinfunction "5_5") (pintype "passive"))
    )
    (net (code "61") (name "unconnected-(JP1-Pad6)") (class "Default")
      (node (ref "JP1") (pin "6") (pinfunction "6_6") (pintype "passive"))
    )
    (net (code "62") (name "unconnected-(JP1-Pad7)") (class "Default")
      (node (ref "JP1") (pin "7") (pinfunction "7_7") (pintype "passive"))
    )
    (net (code "63") (name "unconnected-(JP1-Pad8)") (class "Default")
      (node (ref "JP1") (pin "8") (pinfunction "8_8") (pintype "passive"))
    )
    (net (code "64") (name "unconnected-(JP1-Pad9)") (class "Default")
      (node (ref "JP1") (pin "9") (pinfunction "9_9") (pintype "passive"))
    )
    (net (code "65") (name "unconnected-(JP1-Pad11)") (class "Default")
      (node (ref "JP1") (pin "11") (pinfunction "11_11") (pintype "passive"))
    )
    (net (code "66") (name "unconnected-(JP1-Pad12)") (class "Default")
      (node (ref "JP1") (pin "12") (pinfunction "12_12") (pintype "passive"))
    )
    (net (code "67") (name "unconnected-(JP1-Pad13)") (class "Default")
      (node (ref "JP1") (pin "13") (pinfunction "13_13") (pintype "passive"))
    )
    (net (code "68") (name "unconnected-(JP1-Pad14)") (class "Default")
      (node (ref "JP1") (pin "14") (pinfunction "14_14") (pintype "passive"))
    )
    (net (code "69") (name "unconnected-(JP1-Pad15)") (class "Default")
      (node (ref "JP1") (pin "15") (pinfunction "15_15") (pintype "passive"))
    )
    (net (code "70") (name "unconnected-(JP1-Pad16)") (class "Default")
      (node (ref "JP1") (pin "16") (pinfunction "16_16") (pintype "passive"))
    )
    (net (code "71") (name "unconnected-(JP1-Pad17)") (class "Default")
      (node (ref "JP1") (pin "17") (pinfunction "17_17") (pintype "passive"))
    )
    (net (code "72") (name "unconnected-(JP1-Pad18)") (class "Default")
      (node (ref "JP1") (pin "18") (pinfunction "18_18") (pintype "passive"))
    )
    (net (code "73") (name "unconnected-(JP1-Pad19)") (class "Default")
      (node (ref "JP1") (pin "19") (pinfunction "19_19") (pintype "passive"))
    )
    (net (code "74") (name "unconnected-(JP1-Pad20)") (class "Default")
      (node (ref "JP1") (pin "20") (pinfunction "20_20") (pintype "passive"))
    )
    (net (code "75") (name "unconnected-(JP1-Pad22)") (class "Default")
      (node (ref "JP1") (pin "22") (pinfunction "22_22") (pintype "passive"))
    )
    (net (code "76") (name "unconnected-(JP1-Pad23)") (class "Default")
      (node (ref "JP1") (pin "23") (pinfunction "23_23") (pintype "passive"))
    )
    (net (code "77") (name "unconnected-(JP1-Pad24)") (class "Default")
      (node (ref "JP1") (pin "24") (pinfunction "24_24") (pintype "passive"))
    )
    (net (code "78") (name "unconnected-(JP1-Pad25)") (class "Default")
      (node (ref "JP1") (pin "25") (pinfunction "25_25") (pintype "passive"))
    )
    (net (code "79") (name "unconnected-(JP1-Pad26)") (class "Default")
      (node (ref "JP1") (pin "26") (pinfunction "26_26") (pintype "passive"))
    )
    (net (code "80") (name "unconnected-(JP1-Pad27)") (class "Default")
      (node (ref "JP1") (pin "27") (pinfunction "27_27") (pintype "passive"))
    )
    (net (code "81") (name "unconnected-(JP1-Pad29)") (class "Default")
      (node (ref "JP1") (pin "29") (pinfunction "29_29") (pintype "passive"))
    )
    (net (code "82") (name "unconnected-(JP2-Pad2)") (class "Default")
      (node (ref "JP2") (pin "2") (pinfunction "2_2") (pintype "passive"))
    )
    (net (code "83") (name "unconnected-(JP2-Pad4)") (class "Default")
      (node (ref "JP2") (pin "4") (pinfunction "4_4") (pintype "passive"))
    )
    (net (code "84") (name "unconnected-(JP2-Pad5)") (class "Default")
      (node (ref "JP2") (pin "5") (pinfunction "5_5") (pintype "passive"))
    )
    (net (code "85") (name "unconnected-(JP2-Pad6)") (class "Default")
      (node (ref "JP2") (pin "6") (pinfunction "6_6") (pintype "passive"))
    )
    (net (code "86") (name "unconnected-(JP2-Pad8)") (class "Default")
      (node (ref "JP2") (pin "8") (pinfunction "8_8") (pintype "passive"))
    )
    (net (code "87") (name "unconnected-(JP2-Pad9)") (class "Default")
      (node (ref "JP2") (pin "9") (pinfunction "9_9") (pintype "passive"))
    )
    (net (code "88") (name "unconnected-(JP2-Pad11)") (class "Default")
      (node (ref "JP2") (pin "11") (pinfunction "11_11") (pintype "passive"))
    )
    (net (code "89") (name "unconnected-(JP2-Pad12)") (class "Default")
      (node (ref "JP2") (pin "12") (pinfunction "12_12") (pintype "passive"))
    )
    (net (code "90") (name "unconnected-(JP2-Pad13)") (class "Default")
      (node (ref "JP2") (pin "13") (pinfunction "13_13") (pintype "passive"))
    )
    (net (code "91") (name "unconnected-(JP2-Pad15)") (class "Default")
      (node (ref "JP2") (pin "15") (pinfunction "15_15") (pintype "passive"))
    )
    (net (code "92") (name "unconnected-(JP2-Pad16)") (class "Default")
      (node (ref "JP2") (pin "16") (pinfunction "16_16") (pintype "passive"))
    )
    (net (code "93") (name "unconnected-(JP2-Pad18)") (class "Default")
      (node (ref "JP2") (pin "18") (pinfunction "18_18") (pintype "passive"))
    )
    (net (code "94") (name "unconnected-(JP2-Pad19)") (class "Default")
      (node (ref "JP2") (pin "19") (pinfunction "19_19") (pintype "passive"))
    )
    (net (code "95") (name "unconnected-(JP2-Pad20)") (class "Default")
      (node (ref "JP2") (pin "20") (pinfunction "20_20") (pintype "passive"))
    )
    (net (code "96") (name "unconnected-(JP2-Pad22)") (class "Default")
      (node (ref "JP2") (pin "22") (pinfunction "22_22") (pintype "passive"))
    )
    (net (code "97") (name "unconnected-(JP2-Pad23)") (class "Default")
      (node (ref "JP2") (pin "23") (pinfunction "23_23") (pintype "passive"))
    )
    (net (code "98") (name "unconnected-(JP2-Pad25)") (class "Default")
      (node (ref "JP2") (pin "25") (pinfunction "25_25") (pintype "passive"))
    )
    (net (code "99") (name "unconnected-(JP2-Pad26)") (class "Default")
      (node (ref "JP2") (pin "26") (pinfunction "26_26") (pintype "passive"))
    )
    (net (code "100") (name "unconnected-(JP2-Pad27)") (class "Default")
      (node (ref "JP2") (pin "27") (pinfunction "27_27") (pintype "passive"))
    )
    (net (code "101") (name "unconnected-(JP2-Pad29)") (class "Default")
      (node (ref "JP2") (pin "29") (pinfunction "29_29") (pintype "passive"))
    )
  )
)
